# Lightning_Breakout.net
KiCad netlist of a schematic drawn in EAGLE
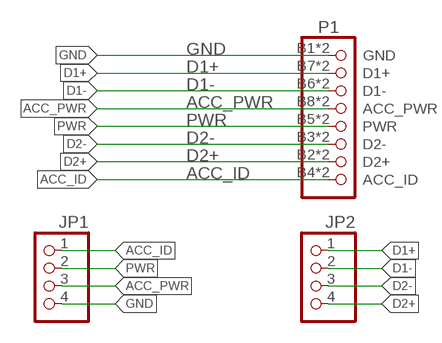
[diagram p0: schematic, sheet 1]

(export (version "E")
  (design (tool "Eeschema 10.0.6"))
  (components
    (comp (ref "JP1")
      (value "PINHD-1X4")
      (footprint "eagle-import:1X04")
      (libsource (lib "eagle-import") (part "PINHD-1X4"))
    )
    (comp (ref "JP2")
      (value "PINHD-1X4")
      (footprint "eagle-import:1X04")
      (libsource (lib "eagle-import") (part "PINHD-1X4"))
    )
    (comp (ref "P1")
      (value "LIGHTNING-8PIN")
      (footprint "eagle-import:LIGHTNING")
      (libsource (lib "eagle-import") (part "LIGHTNING-8PIN"))
    )
  )
  (nets
    (net (code "1") (name "ACC_ID") (class "Default")
      (node (ref "JP1") (pin "1") (pinfunction "1_1") (pintype "passive"))
      (node (ref "P1") (pin "B4") (pinfunction "ACC_ID_B4") (pintype "bidirectional"))
      (node (ref "P1") (pin "T8") (pinfunction "ACC_ID_T8") (pintype "bidirectional"))
    )
    (net (code "2") (name "ACC_PWR") (class "Default")
      (node (ref "JP1") (pin "3") (pinfunction "3_3") (pintype "passive"))
      (node (ref "P1") (pin "B8") (pinfunction "ACC_PWR_B8") (pintype "power_in"))
      (node (ref "P1") (pin "T4") (pinfunction "ACC_PWR_T4") (pintype "power_in"))
    )
    (net (code "3") (name "D1+") (class "Default")
      (node (ref "JP2") (pin "1") (pinfunction "1_1") (pintype "passive"))
      (node (ref "P1") (pin "B7") (pinfunction "D1+_B7") (pintype "bidirectional"))
      (node (ref "P1") (pin "T2") (pinfunction "D1+_T2") (pintype "bidirectional"))
    )
    (net (code "4") (name "D1-") (class "Default")
      (node (ref "JP2") (pin "2") (pinfunction "2_2") (pintype "passive"))
      (node (ref "P1") (pin "B6") (pinfunction "D1-_B6") (pintype "bidirectional"))
      (node (ref "P1") (pin "T3") (pinfunction "D1-_T3") (pintype "bidirectional"))
    )
    (net (code "5") (name "D2+") (class "Default")
      (node (ref "JP2") (pin "4") (pinfunction "4_4") (pintype "passive"))
      (node (ref "P1") (pin "B2") (pinfunction "D2+_B2") (pintype "bidirectional"))
      (node (ref "P1") (pin "T7") (pinfunction "D2+_T7") (pintype "bidirectional"))
    )
    (net (code "6") (name "D2-") (class "Default")
      (node (ref "JP2") (pin "3") (pinfunction "3_3") (pintype "passive"))
      (node (ref "P1") (pin "B3") (pinfunction "D2-_B3") (pintype "bidirectional"))
      (node (ref "P1") (pin "T6") (pinfunction "D2-_T6") (pintype "bidirectional"))
    )
    (net (code "7") (name "GND") (class "Default")
      (node (ref "JP1") (pin "4") (pinfunction "4_4") (pintype "passive"))
      (node (ref "P1") (pin "B1") (pinfunction "GND_B1") (pintype "passive"))
      (node (ref "P1") (pin "T1") (pinfunction "GND_T1") (pintype "passive"))
    )
    (net (code "8") (name "PWR") (class "Default")
      (node (ref "JP1") (pin "2") (pinfunction "2_2") (pintype "passive"))
      (node (ref "P1") (pin "B5") (pinfunction "PWR_B5") (pintype "power_in"))
      (node (ref "P1") (pin "T5") (pinfunction "PWR_T5") (pintype "power_in"))
    )
  )
)
